# DM2097_LEFT_OV9282.net
KiCad netlist of a schematic drawn in Altium Designer
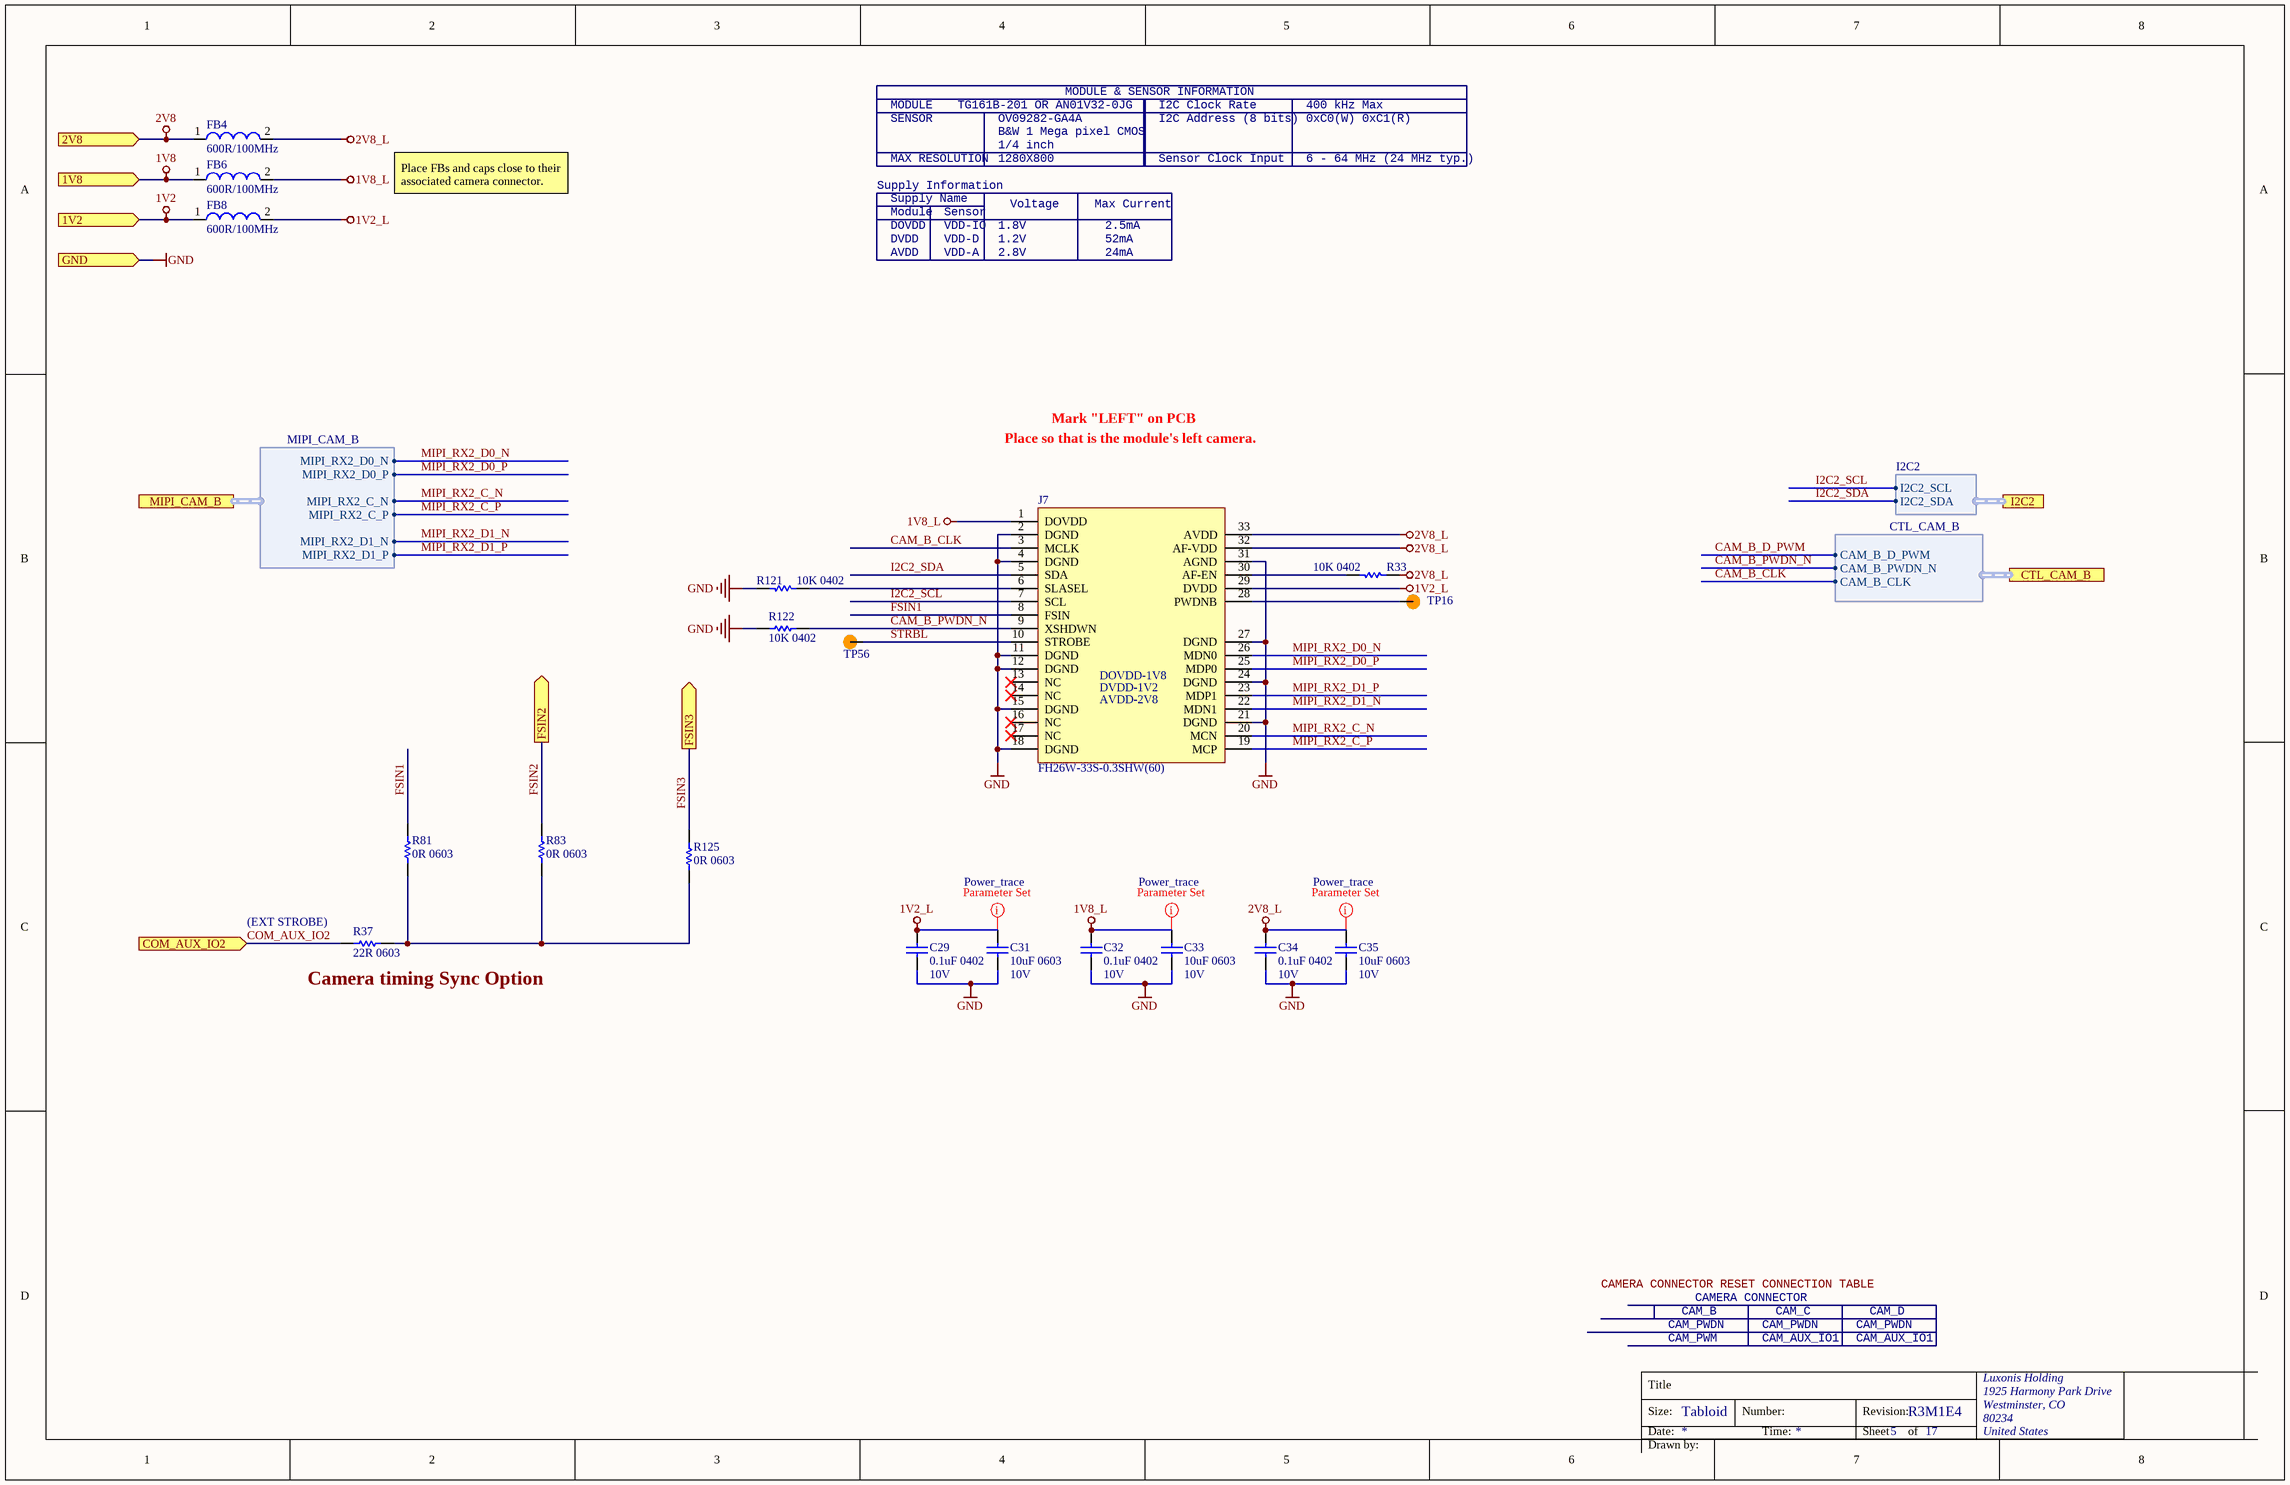
[diagram p0: DM2097_LEFT_OV9282.SchDoc]

(export (version "E")
  (design (tool "Eeschema 10.0.6"))
  (components
    (comp (ref "C29")
      (value "0.1uF 0402")
      (footprint "CAP_Altium_Vault_Generic:CAPC0402(1005)70_N")
      (description "CAP CER 0.1UF 10V X7R 0402 5%")
      (fields (field (name "TOLERANCE") "5%") (field (name "VOLTAGE RATING") "10V"))
      (libsource (lib "LuxonisMaster") (part "GRM155R71A104JA01D"))
    )
    (comp (ref "C31")
      (value "10uF 0603")
      (footprint "CAP_Altium_Vault_Generic:CAPC0603(1608)100_N")
      (description "CAP CER 10UF 10V X5R 0603 20%")
      (fields (field (name "TOLERANCE") "20%") (field (name "VOLTAGE RATING") "10V"))
      (libsource (lib "LuxonisMaster") (part "GRM188R61A106ME69D"))
    )
    (comp (ref "C32")
      (value "0.1uF 0402")
      (footprint "CAP_Altium_Vault_Generic:CAPC0402(1005)70_N")
      (description "CAP CER 0.1UF 10V X7R 0402 5%")
      (fields (field (name "TOLERANCE") "5%") (field (name "VOLTAGE RATING") "10V"))
      (libsource (lib "LuxonisMaster") (part "GRM155R71A104JA01D"))
    )
    (comp (ref "C33")
      (value "10uF 0603")
      (footprint "CAP_Altium_Vault_Generic:CAPC0603(1608)100_N")
      (description "CAP CER 10UF 10V X5R 0603 20%")
      (fields (field (name "TOLERANCE") "20%") (field (name "VOLTAGE RATING") "10V"))
      (libsource (lib "LuxonisMaster") (part "GRM188R61A106ME69D"))
    )
    (comp (ref "C34")
      (value "0.1uF 0402")
      (footprint "CAP_Altium_Vault_Generic:CAPC0402(1005)70_N")
      (description "CAP CER 0.1UF 10V X7R 0402 5%")
      (fields (field (name "TOLERANCE") "5%") (field (name "VOLTAGE RATING") "10V"))
      (libsource (lib "LuxonisMaster") (part "GRM155R71A104JA01D"))
    )
    (comp (ref "C35")
      (value "10uF 0603")
      (footprint "CAP_Altium_Vault_Generic:CAPC0603(1608)100_N")
      (description "CAP CER 10UF 10V X5R 0603 20%")
      (fields (field (name "TOLERANCE") "20%") (field (name "VOLTAGE RATING") "10V"))
      (libsource (lib "LuxonisMaster") (part "GRM188R61A106ME69D"))
    )
    (comp (ref "FB4")
      (value "600R/100MHz")
      (footprint "LuxonisMaster:2508056017Y2")
      (description "FERRITE BEAD, 0.1OHM, 2A, 0805, 600R/100MHz")
      (fields (field (name "TOLERANCE") "25%"))
      (libsource (lib "LuxonisMaster") (part "2508056017Y2"))
    )
    (comp (ref "FB6")
      (value "600R/100MHz")
      (footprint "LuxonisMaster:2508056017Y2")
      (description "FERRITE BEAD, 0.1OHM, 2A, 0805, 600R/100MHz")
      (fields (field (name "TOLERANCE") "25%"))
      (libsource (lib "LuxonisMaster") (part "2508056017Y2"))
    )
    (comp (ref "FB8")
      (value "600R/100MHz")
      (footprint "LuxonisMaster:2508056017Y2")
      (description "FERRITE BEAD, 0.1OHM, 2A, 0805, 600R/100MHz")
      (fields (field (name "TOLERANCE") "25%"))
      (libsource (lib "LuxonisMaster") (part "2508056017Y2"))
    )
    (comp (ref "J7")
      (value "FH26W-33S-0.3SHW(60)")
      (footprint "AC-PY003-OV9282")
      (description "FFC/FPC Connector, 33 Contact(s), 1 Row(s), Female, Right Angle, Surface Mount Terminal")
      (libsource (lib "DM9098") (part "AC_PY003-OV9282_CON"))
    )
    (comp (ref "R33")
      (value "10K 0402")
      (footprint "RES_Altium_Vault_Generic:RESC0402(1005)_L")
      (fields (field (name "TOLERANCE") "1%"))
      (libsource (lib "LuxonisMaster") (part "RC0402FR-1310KL"))
    )
    (comp (ref "R37")
      (value "22R 0603")
      (footprint "RES_Altium_Vault_Generic:RESC0603(1608)_N")
      (description "RES SMD 22 OHM 1% 1/10W 0603")
      (fields (field (name "TOLERANCE") "1%"))
      (libsource (lib "LuxonisMaster") (part "RC0603FR-0722RL"))
    )
    (comp (ref "R81")
      (value "0R 0603")
      (footprint "RES_Altium_Vault_Generic:RESC0603(1608)_N")
      (fields (field (name "TOLERANCE") "5%"))
      (libsource (lib "LuxonisMaster") (part "CRCW06030000Z0EA"))
    )
    (comp (ref "R83")
      (value "0R 0603")
      (footprint "RES_Altium_Vault_Generic:RESC0603(1608)_N")
      (fields (field (name "TOLERANCE") "5%"))
      (libsource (lib "LuxonisMaster") (part "CRCW06030000Z0EA"))
    )
    (comp (ref "R121")
      (value "10K 0402")
      (footprint "RES_Altium_Vault_Generic:RESC0402(1005)_L")
      (fields (field (name "TOLERANCE") "1%"))
      (libsource (lib "LuxonisMaster") (part "RC0402FR-1310KL"))
    )
    (comp (ref "R122")
      (value "10K 0402")
      (footprint "RES_Altium_Vault_Generic:RESC0402(1005)_L")
      (fields (field (name "TOLERANCE") "1%"))
      (libsource (lib "LuxonisMaster") (part "RC0402FR-1310KL"))
    )
    (comp (ref "R125")
      (value "0R 0603")
      (footprint "RES_Altium_Vault_Generic:RESC0603(1608)_N")
      (fields (field (name "TOLERANCE") "5%"))
      (libsource (lib "LuxonisMaster") (part "CRCW06030000Z0EA"))
    )
    (comp (ref "TP16")
      (value "TP100_200_NS")
      (footprint "LuxonisMaster:TP100_200_NS")
      (libsource (lib "LuxonisMaster") (part "TEST_POINT"))
    )
    (comp (ref "TP56")
      (value "TP100_200_NS")
      (footprint "LuxonisMaster:TP100_200_NS")
      (libsource (lib "LuxonisMaster") (part "TEST_POINT"))
    )
  )
  (nets
    (net (code "4") (name "/CAM_B_CLK") (class "Default")
      (node (ref "J7") (pin "3") (pinfunction "MCLK_3") (pintype "passive"))
    )
    (net (code "6") (name "/CAM_B_PWDN_N") (class "Default")
      (node (ref "J7") (pin "9") (pinfunction "XSHDWN_9") (pintype "passive"))
      (node (ref "R122") (pin "1") (pinfunction "1_1") (pintype "passive"))
    )
    (net (code "7") (name "/COM_AUX_IO2") (class "Default")
      (node (ref "R37") (pin "1") (pinfunction "1_1") (pintype "passive"))
    )
    (net (code "8") (name "/FSIN1") (class "Default")
      (node (ref "J7") (pin "8") (pinfunction "FSIN_8") (pintype "passive"))
      (node (ref "R81") (pin "2") (pinfunction "2_2") (pintype "passive"))
    )
    (net (code "9") (name "/FSIN2") (class "Default")
      (node (ref "R83") (pin "2") (pinfunction "2_2") (pintype "passive"))
    )
    (net (code "10") (name "/FSIN3") (class "Default")
      (node (ref "R125") (pin "2") (pinfunction "2_2") (pintype "passive"))
    )
    (net (code "11") (name "/I2C2_SCL") (class "Default")
      (node (ref "J7") (pin "7") (pinfunction "SCL_7") (pintype "passive"))
    )
    (net (code "12") (name "/I2C2_SDA") (class "Default")
      (node (ref "J7") (pin "5") (pinfunction "SDA_5") (pintype "passive"))
    )
    (net (code "13") (name "/MIPI_RX2_C_N") (class "Default")
      (node (ref "J7") (pin "20") (pinfunction "MCN_20") (pintype "passive"))
    )
    (net (code "14") (name "/MIPI_RX2_C_P") (class "Default")
      (node (ref "J7") (pin "19") (pinfunction "MCP_19") (pintype "passive"))
    )
    (net (code "15") (name "/MIPI_RX2_D0_N") (class "Default")
      (node (ref "J7") (pin "26") (pinfunction "MDN0_26") (pintype "passive"))
    )
    (net (code "16") (name "/MIPI_RX2_D0_P") (class "Default")
      (node (ref "J7") (pin "25") (pinfunction "MDP0_25") (pintype "passive"))
    )
    (net (code "17") (name "/MIPI_RX2_D1_N") (class "Default")
      (node (ref "J7") (pin "22") (pinfunction "MDN1_22") (pintype "passive"))
    )
    (net (code "18") (name "/MIPI_RX2_D1_P") (class "Default")
      (node (ref "J7") (pin "23") (pinfunction "MDP1_23") (pintype "passive"))
    )
    (net (code "19") (name "/STRBL") (class "Default")
      (node (ref "J7") (pin "10") (pinfunction "STROBE_10") (pintype "passive"))
      (node (ref "TP56") (pin "1") (pintype "passive"))
    )
    (net (code "23") (name "1V2") (class "Default")
      (node (ref "FB8") (pin "1") (pinfunction "1_1") (pintype "passive"))
    )
    (net (code "24") (name "1V2_L") (class "Default")
      (node (ref "C29") (pin "2") (pinfunction "2_2") (pintype "passive"))
      (node (ref "C31") (pin "2") (pinfunction "2_2") (pintype "passive"))
      (node (ref "FB8") (pin "2") (pinfunction "2_2") (pintype "passive"))
      (node (ref "J7") (pin "29") (pinfunction "DVDD_29") (pintype "passive"))
    )
    (net (code "25") (name "1V8") (class "Default")
      (node (ref "FB6") (pin "1") (pinfunction "1_1") (pintype "passive"))
    )
    (net (code "26") (name "1V8_L") (class "Default")
      (node (ref "C32") (pin "2") (pinfunction "2_2") (pintype "passive"))
      (node (ref "C33") (pin "2") (pinfunction "2_2") (pintype "passive"))
      (node (ref "FB6") (pin "2") (pinfunction "2_2") (pintype "passive"))
      (node (ref "J7") (pin "1") (pinfunction "DOVDD_1") (pintype "passive"))
    )
    (net (code "27") (name "2V8") (class "Default")
      (node (ref "FB4") (pin "1") (pinfunction "1_1") (pintype "passive"))
    )
    (net (code "28") (name "2V8_L") (class "Default")
      (node (ref "C34") (pin "2") (pinfunction "2_2") (pintype "passive"))
      (node (ref "C35") (pin "2") (pinfunction "2_2") (pintype "passive"))
      (node (ref "FB4") (pin "2") (pinfunction "2_2") (pintype "passive"))
      (node (ref "J7") (pin "32") (pinfunction "AF-VDD_32") (pintype "passive"))
      (node (ref "J7") (pin "33") (pinfunction "AVDD_33") (pintype "passive"))
      (node (ref "R33") (pin "2") (pinfunction "2_2") (pintype "passive"))
    )
    (net (code "29") (name "GND") (class "Default")
      (node (ref "C29") (pin "1") (pinfunction "1_1") (pintype "passive"))
      (node (ref "C31") (pin "1") (pinfunction "1_1") (pintype "passive"))
      (node (ref "C32") (pin "1") (pinfunction "1_1") (pintype "passive"))
      (node (ref "C33") (pin "1") (pinfunction "1_1") (pintype "passive"))
      (node (ref "C34") (pin "1") (pinfunction "1_1") (pintype "passive"))
      (node (ref "C35") (pin "1") (pinfunction "1_1") (pintype "passive"))
      (node (ref "J7") (pin "11") (pinfunction "DGND_11") (pintype "passive"))
      (node (ref "J7") (pin "12") (pinfunction "DGND_12") (pintype "passive"))
      (node (ref "J7") (pin "15") (pinfunction "DGND_15") (pintype "passive"))
      (node (ref "J7") (pin "18") (pinfunction "DGND_18") (pintype "passive"))
      (node (ref "J7") (pin "2") (pinfunction "DGND_2") (pintype "passive"))
      (node (ref "J7") (pin "21") (pinfunction "DGND_21") (pintype "passive"))
      (node (ref "J7") (pin "24") (pinfunction "DGND_24") (pintype "passive"))
      (node (ref "J7") (pin "27") (pinfunction "DGND_27") (pintype "passive"))
      (node (ref "J7") (pin "31") (pinfunction "AGND_31") (pintype "passive"))
      (node (ref "J7") (pin "4") (pinfunction "DGND_4") (pintype "passive"))
      (node (ref "R121") (pin "1") (pinfunction "1_1") (pintype "passive"))
      (node (ref "R122") (pin "2") (pinfunction "2_2") (pintype "passive"))
    )
    (net (code "30") (name "Net-(J7-AF-EN)") (class "Default")
      (node (ref "J7") (pin "30") (pinfunction "AF-EN_30") (pintype "passive"))
      (node (ref "R33") (pin "1") (pinfunction "1_1") (pintype "passive"))
    )
    (net (code "31") (name "Net-(J7-PWDNB)") (class "Default")
      (node (ref "J7") (pin "28") (pinfunction "PWDNB_28") (pintype "passive"))
      (node (ref "TP16") (pin "1") (pintype "passive"))
    )
    (net (code "32") (name "Net-(J7-SLASEL)") (class "Default")
      (node (ref "J7") (pin "6") (pinfunction "SLASEL_6") (pintype "passive"))
      (node (ref "R121") (pin "2") (pinfunction "2_2") (pintype "passive"))
    )
    (net (code "33") (name "Net-(R125-Pad1)") (class "Default")
      (node (ref "R125") (pin "1") (pinfunction "1_1") (pintype "passive"))
      (node (ref "R37") (pin "2") (pinfunction "2_2") (pintype "passive"))
      (node (ref "R81") (pin "1") (pinfunction "1_1") (pintype "passive"))
      (node (ref "R83") (pin "1") (pinfunction "1_1") (pintype "passive"))
    )
    (net (code "34") (name "unconnected-(J7-NC-Pad13)") (class "Default")
      (node (ref "J7") (pin "13") (pinfunction "NC_13") (pintype "passive+no_connect"))
    )
    (net (code "35") (name "unconnected-(J7-NC-Pad14)") (class "Default")
      (node (ref "J7") (pin "14") (pinfunction "NC_14") (pintype "passive+no_connect"))
    )
    (net (code "36") (name "unconnected-(J7-NC-Pad16)") (class "Default")
      (node (ref "J7") (pin "16") (pinfunction "NC_16") (pintype "passive+no_connect"))
    )
    (net (code "37") (name "unconnected-(J7-NC-Pad17)") (class "Default")
      (node (ref "J7") (pin "17") (pinfunction "NC_17") (pintype "passive+no_connect"))
    )
  )
)
